# Sheet1.net
KiCad netlist of a schematic drawn in Altium Designer
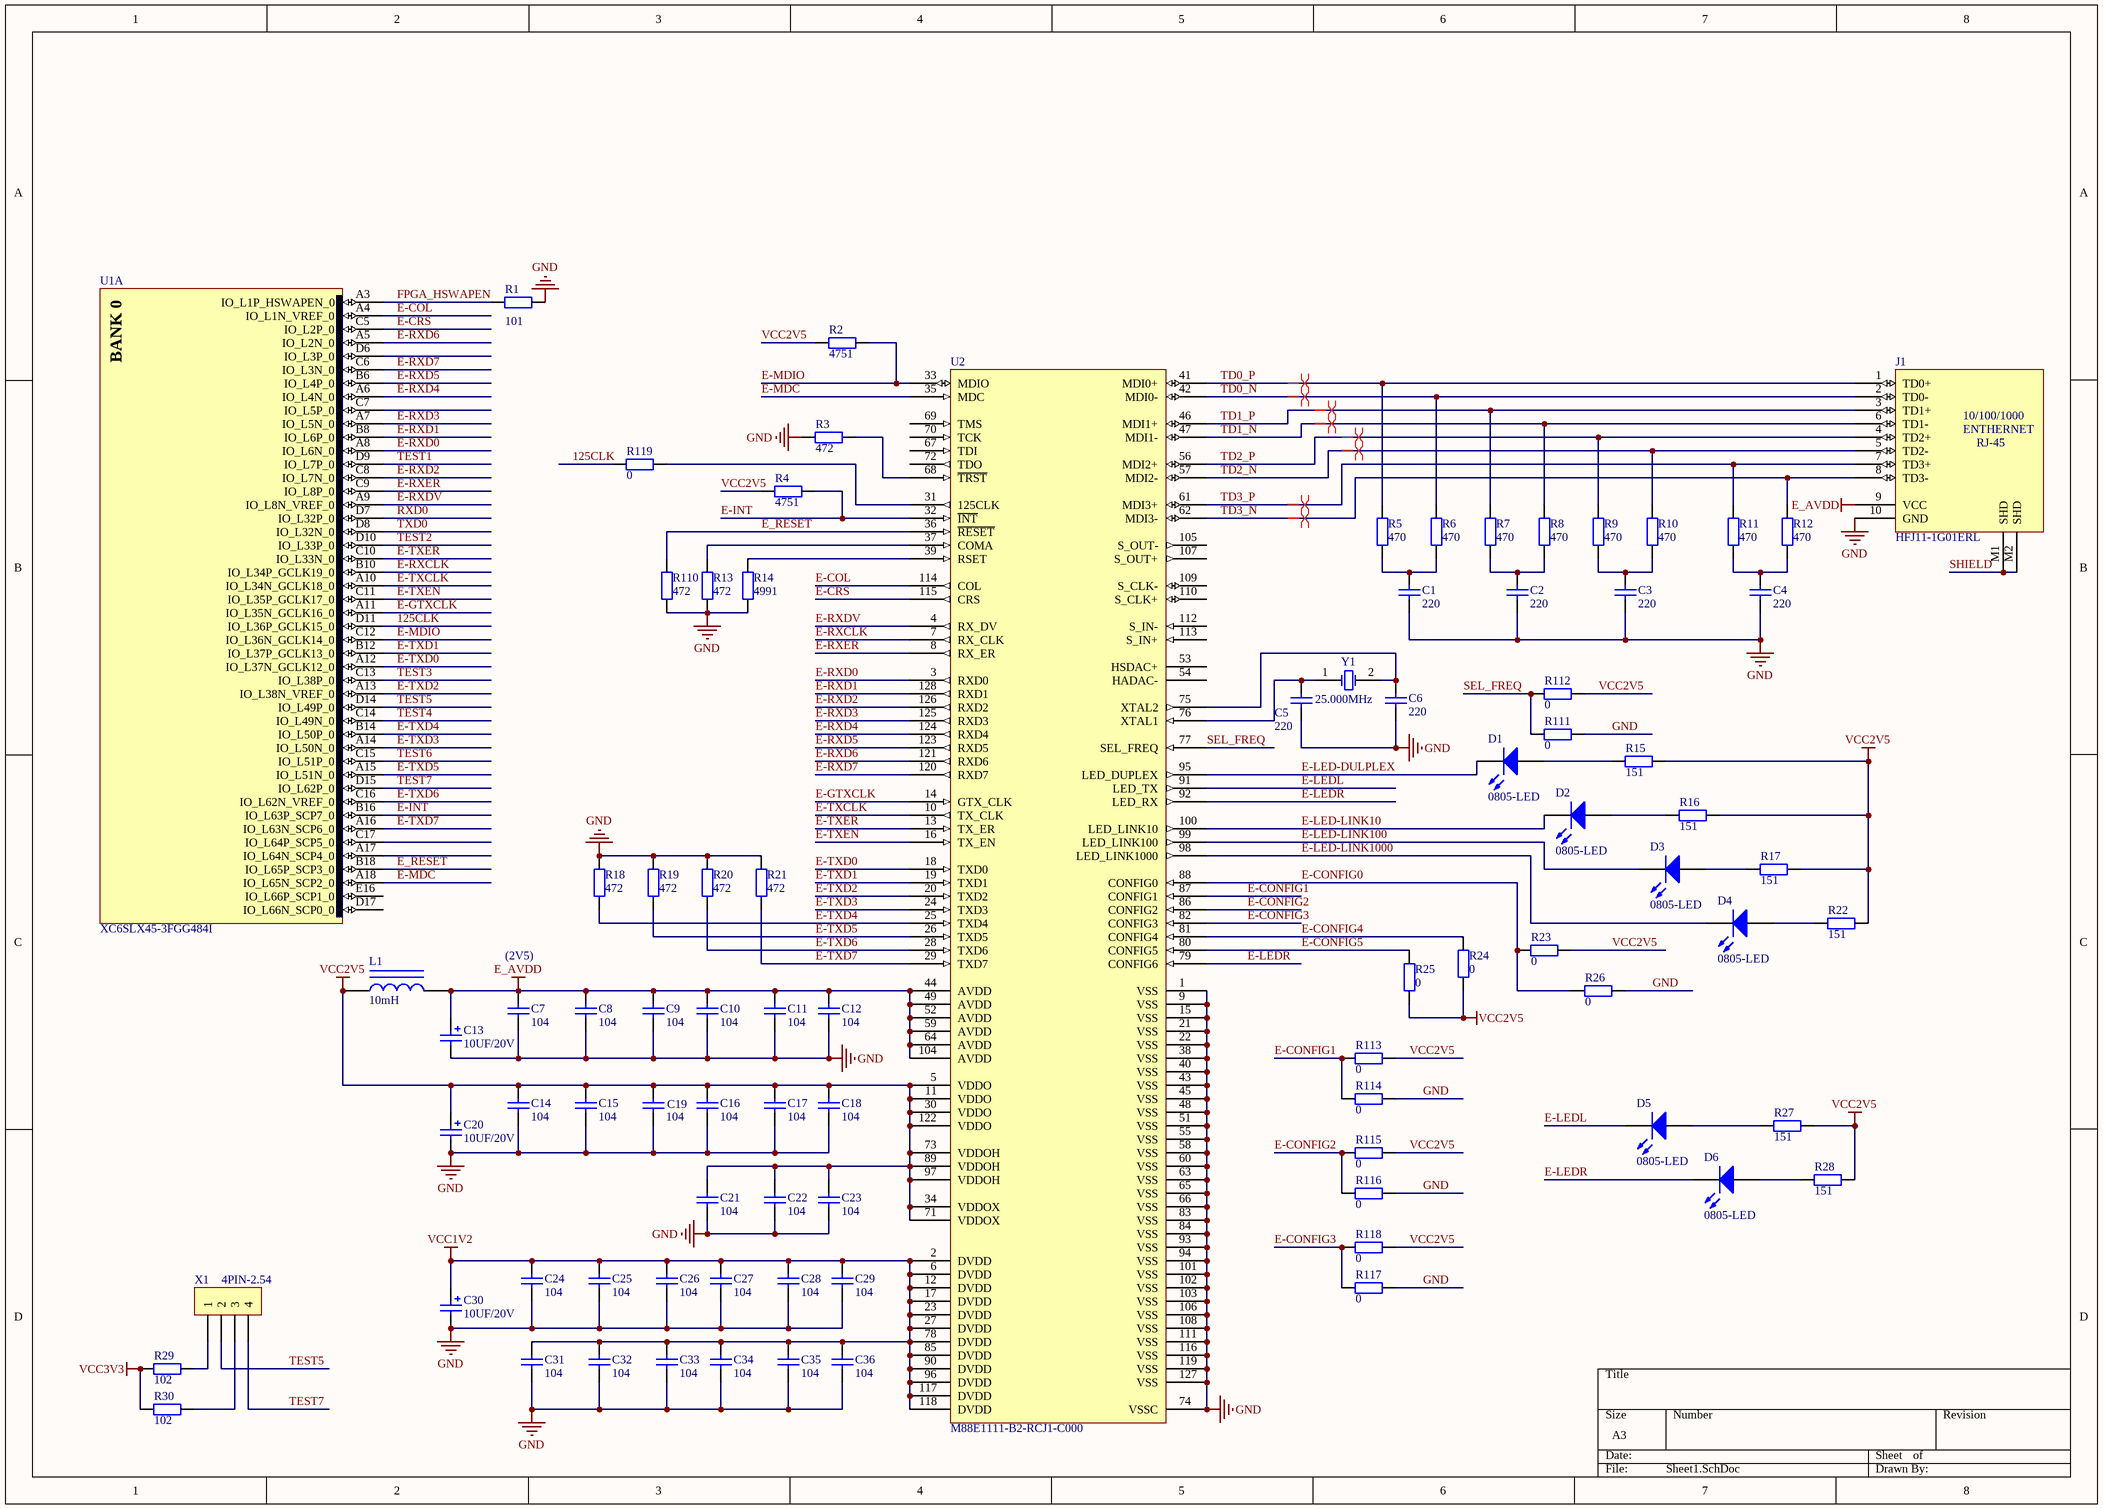
[diagram p0: Sheet1.SchDoc]

(export (version "E")
  (design (tool "Eeschema 10.0.6"))
  (components
    (comp (ref "C1")
      (value "220")
      (footprint "0402")
      (description "Capacitor")
      (fields (field (name "PUBLISHER") "Altium Limited"))
      (libsource (lib "Miscellaneous Devices") (part "Cap"))
    )
    (comp (ref "C2")
      (value "220")
      (footprint "0402")
      (description "Capacitor")
      (fields (field (name "PUBLISHER") "Altium Limited"))
      (libsource (lib "Miscellaneous Devices") (part "Cap"))
    )
    (comp (ref "C3")
      (value "220")
      (footprint "0402")
      (description "Capacitor")
      (fields (field (name "PUBLISHER") "Altium Limited"))
      (libsource (lib "Miscellaneous Devices") (part "Cap"))
    )
    (comp (ref "C4")
      (value "220")
      (footprint "0402")
      (description "Capacitor")
      (fields (field (name "PUBLISHER") "Altium Limited"))
      (libsource (lib "Miscellaneous Devices") (part "Cap"))
    )
    (comp (ref "C5")
      (value "220")
      (footprint "0402")
      (description "Capacitor")
      (fields (field (name "PUBLISHER") "Altium Limited"))
      (libsource (lib "Miscellaneous Devices") (part "Cap"))
    )
    (comp (ref "C6")
      (value "220")
      (footprint "0402")
      (description "Capacitor")
      (fields (field (name "PUBLISHER") "Altium Limited"))
      (libsource (lib "Miscellaneous Devices") (part "Cap"))
    )
    (comp (ref "C7")
      (value "104")
      (footprint "0402")
      (description "Capacitor")
      (fields (field (name "PUBLISHER") "Altium Limited"))
      (libsource (lib "Miscellaneous Devices") (part "Cap"))
    )
    (comp (ref "C8")
      (value "104")
      (footprint "0402")
      (description "Capacitor")
      (fields (field (name "PUBLISHER") "Altium Limited"))
      (libsource (lib "Miscellaneous Devices") (part "Cap"))
    )
    (comp (ref "C9")
      (value "104")
      (footprint "0402")
      (description "Capacitor")
      (fields (field (name "PUBLISHER") "Altium Limited"))
      (libsource (lib "Miscellaneous Devices") (part "Cap"))
    )
    (comp (ref "C10")
      (value "104")
      (footprint "0402")
      (description "Capacitor")
      (fields (field (name "PUBLISHER") "Altium Limited"))
      (libsource (lib "Miscellaneous Devices") (part "Cap"))
    )
    (comp (ref "C11")
      (value "104")
      (footprint "0402")
      (description "Capacitor")
      (fields (field (name "PUBLISHER") "Altium Limited"))
      (libsource (lib "Miscellaneous Devices") (part "Cap"))
    )
    (comp (ref "C12")
      (value "104")
      (footprint "0402")
      (description "Capacitor")
      (fields (field (name "PUBLISHER") "Altium Limited"))
      (libsource (lib "Miscellaneous Devices") (part "Cap"))
    )
    (comp (ref "C13")
      (value "10UF/20V")
      (footprint "CAP-B")
      (description "Polarized Capacitor (Axial)")
      (fields (field (name "PUBLISHER") "Altium Limited"))
      (libsource (lib "Miscellaneous Devices") (part "Cap Pol2"))
    )
    (comp (ref "C14")
      (value "104")
      (footprint "0402")
      (description "Capacitor")
      (fields (field (name "PUBLISHER") "Altium Limited"))
      (libsource (lib "Miscellaneous Devices") (part "Cap"))
    )
    (comp (ref "C15")
      (value "104")
      (footprint "0402")
      (description "Capacitor")
      (fields (field (name "PUBLISHER") "Altium Limited"))
      (libsource (lib "Miscellaneous Devices") (part "Cap"))
    )
    (comp (ref "C16")
      (value "104")
      (footprint "0402")
      (description "Capacitor")
      (fields (field (name "PUBLISHER") "Altium Limited"))
      (libsource (lib "Miscellaneous Devices") (part "Cap"))
    )
    (comp (ref "C17")
      (value "104")
      (footprint "0402")
      (description "Capacitor")
      (fields (field (name "PUBLISHER") "Altium Limited"))
      (libsource (lib "Miscellaneous Devices") (part "Cap"))
    )
    (comp (ref "C18")
      (value "104")
      (footprint "0402")
      (description "Capacitor")
      (fields (field (name "PUBLISHER") "Altium Limited"))
      (libsource (lib "Miscellaneous Devices") (part "Cap"))
    )
    (comp (ref "C19")
      (value "104")
      (footprint "0402")
      (description "Capacitor")
      (fields (field (name "PUBLISHER") "Altium Limited"))
      (libsource (lib "Miscellaneous Devices") (part "Cap"))
    )
    (comp (ref "C20")
      (value "10UF/20V")
      (footprint "CAP-B")
      (description "Polarized Capacitor (Axial)")
      (fields (field (name "PUBLISHER") "Altium Limited"))
      (libsource (lib "Miscellaneous Devices") (part "Cap Pol2"))
    )
    (comp (ref "C21")
      (value "104")
      (footprint "0402")
      (description "Capacitor")
      (fields (field (name "PUBLISHER") "Altium Limited"))
      (libsource (lib "Miscellaneous Devices") (part "Cap"))
    )
    (comp (ref "C22")
      (value "104")
      (footprint "0402")
      (description "Capacitor")
      (fields (field (name "PUBLISHER") "Altium Limited"))
      (libsource (lib "Miscellaneous Devices") (part "Cap"))
    )
    (comp (ref "C23")
      (value "104")
      (footprint "0402")
      (description "Capacitor")
      (fields (field (name "PUBLISHER") "Altium Limited"))
      (libsource (lib "Miscellaneous Devices") (part "Cap"))
    )
    (comp (ref "C24")
      (value "104")
      (footprint "0402")
      (description "Capacitor")
      (fields (field (name "PUBLISHER") "Altium Limited"))
      (libsource (lib "Miscellaneous Devices") (part "Cap"))
    )
    (comp (ref "C25")
      (value "104")
      (footprint "0402")
      (description "Capacitor")
      (fields (field (name "PUBLISHER") "Altium Limited"))
      (libsource (lib "Miscellaneous Devices") (part "Cap"))
    )
    (comp (ref "C26")
      (value "104")
      (footprint "0402")
      (description "Capacitor")
      (fields (field (name "PUBLISHER") "Altium Limited"))
      (libsource (lib "Miscellaneous Devices") (part "Cap"))
    )
    (comp (ref "C27")
      (value "104")
      (footprint "0402")
      (description "Capacitor")
      (fields (field (name "PUBLISHER") "Altium Limited"))
      (libsource (lib "Miscellaneous Devices") (part "Cap"))
    )
    (comp (ref "C28")
      (value "104")
      (footprint "0402")
      (description "Capacitor")
      (fields (field (name "PUBLISHER") "Altium Limited"))
      (libsource (lib "Miscellaneous Devices") (part "Cap"))
    )
    (comp (ref "C29")
      (value "104")
      (footprint "0402")
      (description "Capacitor")
      (fields (field (name "PUBLISHER") "Altium Limited"))
      (libsource (lib "Miscellaneous Devices") (part "Cap"))
    )
    (comp (ref "C30")
      (value "10UF/20V")
      (footprint "CAP-B")
      (description "Polarized Capacitor (Axial)")
      (fields (field (name "PUBLISHER") "Altium Limited"))
      (libsource (lib "Miscellaneous Devices") (part "Cap Pol2"))
    )
    (comp (ref "C31")
      (value "104")
      (footprint "0402")
      (description "Capacitor")
      (fields (field (name "PUBLISHER") "Altium Limited"))
      (libsource (lib "Miscellaneous Devices") (part "Cap"))
    )
    (comp (ref "C32")
      (value "104")
      (footprint "0402")
      (description "Capacitor")
      (fields (field (name "PUBLISHER") "Altium Limited"))
      (libsource (lib "Miscellaneous Devices") (part "Cap"))
    )
    (comp (ref "C33")
      (value "104")
      (footprint "0402")
      (description "Capacitor")
      (fields (field (name "PUBLISHER") "Altium Limited"))
      (libsource (lib "Miscellaneous Devices") (part "Cap"))
    )
    (comp (ref "C34")
      (value "104")
      (footprint "0402")
      (description "Capacitor")
      (fields (field (name "PUBLISHER") "Altium Limited"))
      (libsource (lib "Miscellaneous Devices") (part "Cap"))
    )
    (comp (ref "C35")
      (value "104")
      (footprint "0402")
      (description "Capacitor")
      (fields (field (name "PUBLISHER") "Altium Limited"))
      (libsource (lib "Miscellaneous Devices") (part "Cap"))
    )
    (comp (ref "C36")
      (value "104")
      (footprint "0402")
      (description "Capacitor")
      (fields (field (name "PUBLISHER") "Altium Limited"))
      (libsource (lib "Miscellaneous Devices") (part "Cap"))
    )
    (comp (ref "D1")
      (value "0805-LED")
      (footprint "0805LED")
      (description "Typical INFRARED GaAs LED")
      (fields (field (name "PUBLISHER") "Altium Limited"))
      (libsource (lib "Miscellaneous Devices") (part "LED0"))
    )
    (comp (ref "D2")
      (value "0805-LED")
      (footprint "0805LED")
      (description "Typical INFRARED GaAs LED")
      (fields (field (name "PUBLISHER") "Altium Limited"))
      (libsource (lib "Miscellaneous Devices") (part "LED0"))
    )
    (comp (ref "D3")
      (value "0805-LED")
      (footprint "0805LED")
      (description "Typical INFRARED GaAs LED")
      (fields (field (name "PUBLISHER") "Altium Limited"))
      (libsource (lib "Miscellaneous Devices") (part "LED0"))
    )
    (comp (ref "D4")
      (value "0805-LED")
      (footprint "0805LED")
      (description "Typical INFRARED GaAs LED")
      (fields (field (name "PUBLISHER") "Altium Limited"))
      (libsource (lib "Miscellaneous Devices") (part "LED0"))
    )
    (comp (ref "D5")
      (value "0805-LED")
      (footprint "0805LED")
      (description "Typical INFRARED GaAs LED")
      (fields (field (name "PUBLISHER") "Altium Limited"))
      (libsource (lib "Miscellaneous Devices") (part "LED0"))
    )
    (comp (ref "D6")
      (value "0805-LED")
      (footprint "0805LED")
      (description "Typical INFRARED GaAs LED")
      (fields (field (name "PUBLISHER") "Altium Limited"))
      (libsource (lib "Miscellaneous Devices") (part "LED0"))
    )
    (comp (ref "J1")
      (value "HFJ11-1G01ERL")
      (footprint "HFJ11-1G01ERL")
      (libsource (lib "Schlib1") (part "ETHERNET-RJ45"))
    )
    (comp (ref "L1")
      (value "10mH")
      (footprint "1206A")
      (description "Magnetic-Core Inductor")
      (fields (field (name "PUBLISHER") "Altium Limited"))
      (libsource (lib "Miscellaneous Devices") (part "Inductor Iron"))
    )
    (comp (ref "R1")
      (value "101")
      (footprint "0603")
      (description "Resistor")
      (fields (field (name "PUBLISHER") "Altium Limited"))
      (libsource (lib "Miscellaneous Devices") (part "Res2"))
    )
    (comp (ref "R2")
      (value "4751")
      (footprint "0603")
      (description "Resistor")
      (fields (field (name "PUBLISHER") "Altium Limited"))
      (libsource (lib "") (part "Res2_3"))
    )
    (comp (ref "R3")
      (value "472")
      (footprint "0603")
      (description "Resistor")
      (fields (field (name "PUBLISHER") "Altium Limited"))
      (libsource (lib "") (part "Res2_3"))
    )
    (comp (ref "R4")
      (value "4751")
      (footprint "0603")
      (description "Resistor")
      (fields (field (name "PUBLISHER") "Altium Limited"))
      (libsource (lib "") (part "Res2_3"))
    )
    (comp (ref "R5")
      (value "470")
      (footprint "0603")
      (description "Resistor")
      (fields (field (name "PUBLISHER") "Altium Limited"))
      (libsource (lib "") (part "Res2_1"))
    )
    (comp (ref "R6")
      (value "470")
      (footprint "0603")
      (description "Resistor")
      (fields (field (name "PUBLISHER") "Altium Limited"))
      (libsource (lib "") (part "Res2_1"))
    )
    (comp (ref "R7")
      (value "470")
      (footprint "0603")
      (description "Resistor")
      (fields (field (name "PUBLISHER") "Altium Limited"))
      (libsource (lib "") (part "Res2_1"))
    )
    (comp (ref "R8")
      (value "470")
      (footprint "0603")
      (description "Resistor")
      (fields (field (name "PUBLISHER") "Altium Limited"))
      (libsource (lib "") (part "Res2_1"))
    )
    (comp (ref "R9")
      (value "470")
      (footprint "0603")
      (description "Resistor")
      (fields (field (name "PUBLISHER") "Altium Limited"))
      (libsource (lib "") (part "Res2_1"))
    )
    (comp (ref "R10")
      (value "470")
      (footprint "0603")
      (description "Resistor")
      (fields (field (name "PUBLISHER") "Altium Limited"))
      (libsource (lib "") (part "Res2_1"))
    )
    (comp (ref "R11")
      (value "470")
      (footprint "0603")
      (description "Resistor")
      (fields (field (name "PUBLISHER") "Altium Limited"))
      (libsource (lib "") (part "Res2_1"))
    )
    (comp (ref "R12")
      (value "470")
      (footprint "0603")
      (description "Resistor")
      (fields (field (name "PUBLISHER") "Altium Limited"))
      (libsource (lib "") (part "Res2_1"))
    )
    (comp (ref "R13")
      (value "472")
      (footprint "0603")
      (description "Resistor")
      (fields (field (name "PUBLISHER") "Altium Limited"))
      (libsource (lib "") (part "Res2_1"))
    )
    (comp (ref "R14")
      (value "4991")
      (footprint "0603")
      (description "Resistor")
      (fields (field (name "PUBLISHER") "Altium Limited"))
      (libsource (lib "") (part "Res2_1"))
    )
    (comp (ref "R15")
      (value "151")
      (footprint "0603")
      (description "Resistor")
      (fields (field (name "PUBLISHER") "Altium Limited"))
      (libsource (lib "Miscellaneous Devices") (part "Res2"))
    )
    (comp (ref "R16")
      (value "151")
      (footprint "0603")
      (description "Resistor")
      (fields (field (name "PUBLISHER") "Altium Limited"))
      (libsource (lib "Miscellaneous Devices") (part "Res2"))
    )
    (comp (ref "R17")
      (value "151")
      (footprint "0603")
      (description "Resistor")
      (fields (field (name "PUBLISHER") "Altium Limited"))
      (libsource (lib "Miscellaneous Devices") (part "Res2"))
    )
    (comp (ref "R18")
      (value "472")
      (footprint "0603")
      (description "Resistor")
      (fields (field (name "PUBLISHER") "Altium Limited"))
      (libsource (lib "") (part "Res2_1"))
    )
    (comp (ref "R19")
      (value "472")
      (footprint "0603")
      (description "Resistor")
      (fields (field (name "PUBLISHER") "Altium Limited"))
      (libsource (lib "") (part "Res2_1"))
    )
    (comp (ref "R20")
      (value "472")
      (footprint "0603")
      (description "Resistor")
      (fields (field (name "PUBLISHER") "Altium Limited"))
      (libsource (lib "") (part "Res2_1"))
    )
    (comp (ref "R21")
      (value "472")
      (footprint "0603")
      (description "Resistor")
      (fields (field (name "PUBLISHER") "Altium Limited"))
      (libsource (lib "") (part "Res2_1"))
    )
    (comp (ref "R22")
      (value "151")
      (footprint "0603")
      (description "Resistor")
      (fields (field (name "PUBLISHER") "Altium Limited"))
      (libsource (lib "Miscellaneous Devices") (part "Res2"))
    )
    (comp (ref "R23")
      (value "0")
      (footprint "0603")
      (description "Resistor")
      (fields (field (name "PUBLISHER") "Altium Limited"))
      (libsource (lib "Miscellaneous Devices") (part "Res2"))
    )
    (comp (ref "R24")
      (value "0")
      (footprint "0603")
      (description "Resistor")
      (fields (field (name "PUBLISHER") "Altium Limited"))
      (libsource (lib "") (part "Res2_2"))
    )
    (comp (ref "R25")
      (value "0")
      (footprint "0603")
      (description "Resistor")
      (fields (field (name "PUBLISHER") "Altium Limited"))
      (libsource (lib "") (part "Res2_2"))
    )
    (comp (ref "R26")
      (value "0")
      (footprint "0603")
      (description "Resistor")
      (fields (field (name "PUBLISHER") "Altium Limited"))
      (libsource (lib "Miscellaneous Devices") (part "Res2"))
    )
    (comp (ref "R27")
      (value "151")
      (footprint "0603")
      (description "Resistor")
      (fields (field (name "PUBLISHER") "Altium Limited"))
      (libsource (lib "Miscellaneous Devices") (part "Res2"))
    )
    (comp (ref "R28")
      (value "151")
      (footprint "0603")
      (description "Resistor")
      (fields (field (name "PUBLISHER") "Altium Limited"))
      (libsource (lib "Miscellaneous Devices") (part "Res2"))
    )
    (comp (ref "R29")
      (value "102")
      (footprint "0603")
      (description "Resistor")
      (fields (field (name "PUBLISHER") "Altium Limited"))
      (libsource (lib "") (part "Res2_3"))
    )
    (comp (ref "R30")
      (value "102")
      (footprint "0603")
      (description "Resistor")
      (fields (field (name "PUBLISHER") "Altium Limited"))
      (libsource (lib "") (part "Res2_3"))
    )
    (comp (ref "R110")
      (value "472")
      (footprint "0603")
      (description "Resistor")
      (fields (field (name "PUBLISHER") "Altium Limited"))
      (libsource (lib "") (part "Res2_1"))
    )
    (comp (ref "R111")
      (value "0")
      (footprint "0402")
      (description "Resistor")
      (fields (field (name "PUBLISHER") "Altium Limited"))
      (libsource (lib "Miscellaneous Devices") (part "Res2"))
    )
    (comp (ref "R112")
      (value "0")
      (footprint "0402")
      (description "Resistor")
      (fields (field (name "PUBLISHER") "Altium Limited"))
      (libsource (lib "Miscellaneous Devices") (part "Res2"))
    )
    (comp (ref "R113")
      (value "0")
      (footprint "0402")
      (description "Resistor")
      (fields (field (name "PUBLISHER") "Altium Limited"))
      (libsource (lib "Miscellaneous Devices") (part "Res2"))
    )
    (comp (ref "R114")
      (value "0")
      (footprint "0402")
      (description "Resistor")
      (fields (field (name "PUBLISHER") "Altium Limited"))
      (libsource (lib "Miscellaneous Devices") (part "Res2"))
    )
    (comp (ref "R115")
      (value "0")
      (footprint "0402")
      (description "Resistor")
      (fields (field (name "PUBLISHER") "Altium Limited"))
      (libsource (lib "Miscellaneous Devices") (part "Res2"))
    )
    (comp (ref "R116")
      (value "0")
      (footprint "0402")
      (description "Resistor")
      (fields (field (name "PUBLISHER") "Altium Limited"))
      (libsource (lib "Miscellaneous Devices") (part "Res2"))
    )
    (comp (ref "R117")
      (value "0")
      (footprint "0402")
      (description "Resistor")
      (fields (field (name "PUBLISHER") "Altium Limited"))
      (libsource (lib "Miscellaneous Devices") (part "Res2"))
    )
    (comp (ref "R118")
      (value "0")
      (footprint "0402")
      (description "Resistor")
      (fields (field (name "PUBLISHER") "Altium Limited"))
      (libsource (lib "Miscellaneous Devices") (part "Res2"))
    )
    (comp (ref "R119")
      (value "0")
      (footprint "0603")
      (description "Resistor")
      (fields (field (name "PUBLISHER") "Altium Limited"))
      (libsource (lib "Miscellaneous Devices") (part "Res2"))
    )
    (comp (ref "U1")
      (value "XC6SLX45-3FGG484I")
      (footprint "FGG484")
      (fields (field (name "PUBLISHER") "Altium Limited"))
      (libsource (lib "Xilinx Spartan-6") (part "XC6SLX45-3FGG484I"))
    )
    (comp (ref "U2")
      (value "M88E1111-B2-RCJ1-C000")
      (footprint "SQFP50P1720X2320-128L")
      (libsource (lib "Schlib1") (part "Component_1"))
    )
    (comp (ref "X1")
      (value "4PIN-2.54")
      (footprint "SIP4X")
      (description "Connector")
      (libsource (lib "*") (part "CON4"))
    )
    (comp (ref "Y1")
      (value "25.000MHz")
      (footprint "CRYSTAL_2")
      (description "Crystal Oscillator")
      (fields (field (name "PUBLISHER") "Altium Limited"))
      (libsource (lib "Miscellaneous Devices") (part "XTAL"))
    )
  )
  (nets
    (net (code "1") (name "/125CLK") (class "Default")
      (node (ref "R119") (pin "2") (pinfunction "2_2") (pintype "passive"))
      (node (ref "U1") (pin "D11") (pinfunction "IO_L36P_GCLK15_0_D11") (pintype "bidirectional"))
    )
    (net (code "2") (name "/E-COL") (class "Default")
      (node (ref "U1") (pin "A4") (pinfunction "IO_L1N_VREF_0_A4") (pintype "bidirectional"))
      (node (ref "U2") (pin "114") (pinfunction "COL_114") (pintype "output"))
    )
    (net (code "3") (name "/E-CONFIG0") (class "Default")
      (node (ref "R23") (pin "2") (pinfunction "2_2") (pintype "passive"))
      (node (ref "R26") (pin "2") (pinfunction "2_2") (pintype "passive"))
      (node (ref "U2") (pin "88") (pinfunction "CONFIG0_88") (pintype "input"))
    )
    (net (code "4") (name "/E-CONFIG1") (class "Default")
      (node (ref "R113") (pin "2") (pinfunction "2_2") (pintype "passive"))
      (node (ref "R114") (pin "2") (pinfunction "2_2") (pintype "passive"))
      (node (ref "U2") (pin "87") (pinfunction "CONFIG1_87") (pintype "input"))
    )
    (net (code "5") (name "/E-CONFIG2") (class "Default")
      (node (ref "R115") (pin "2") (pinfunction "2_2") (pintype "passive"))
      (node (ref "R116") (pin "2") (pinfunction "2_2") (pintype "passive"))
      (node (ref "U2") (pin "86") (pinfunction "CONFIG2_86") (pintype "input"))
    )
    (net (code "6") (name "/E-CONFIG3") (class "Default")
      (node (ref "R117") (pin "2") (pinfunction "2_2") (pintype "passive"))
      (node (ref "R118") (pin "2") (pinfunction "2_2") (pintype "passive"))
      (node (ref "U2") (pin "82") (pinfunction "CONFIG3_82") (pintype "input"))
    )
    (net (code "7") (name "/E-CONFIG4") (class "Default")
      (node (ref "R24") (pin "1") (pinfunction "1_1") (pintype "passive"))
      (node (ref "U2") (pin "81") (pinfunction "CONFIG4_81") (pintype "input"))
    )
    (net (code "8") (name "/E-CONFIG5") (class "Default")
      (node (ref "R25") (pin "1") (pinfunction "1_1") (pintype "passive"))
      (node (ref "U2") (pin "80") (pinfunction "CONFIG5_80") (pintype "input"))
    )
    (net (code "9") (name "/E-CRS") (class "Default")
      (node (ref "U1") (pin "C5") (pinfunction "IO_L2P_0_C5") (pintype "bidirectional"))
      (node (ref "U2") (pin "115") (pinfunction "CRS_115") (pintype "output"))
    )
    (net (code "10") (name "/E-GTXCLK") (class "Default")
      (node (ref "U1") (pin "A11") (pinfunction "IO_L35N_GCLK16_0_A11") (pintype "bidirectional"))
      (node (ref "U2") (pin "14") (pinfunction "GTX_CLK_14") (pintype "input"))
    )
    (net (code "11") (name "/E-INT") (class "Default")
      (node (ref "R4") (pin "2") (pinfunction "2_2") (pintype "passive"))
      (node (ref "U1") (pin "B16") (pinfunction "IO_L63P_SCP7_0_B16") (pintype "bidirectional"))
      (node (ref "U2") (pin "32") (pinfunction "~{INT}_32") (pintype "input"))
    )
    (net (code "12") (name "/E-LED-DULPLEX") (class "Default")
      (node (ref "D1") (pin "2") (pinfunction "K_2") (pintype "passive"))
      (node (ref "U2") (pin "95") (pinfunction "LED_DUPLEX_95") (pintype "output"))
    )
    (net (code "13") (name "/E-LED-LINK10") (class "Default")
      (node (ref "D2") (pin "2") (pinfunction "K_2") (pintype "passive"))
      (node (ref "U2") (pin "100") (pinfunction "LED_LINK10_100") (pintype "output"))
    )
    (net (code "14") (name "/E-LED-LINK100") (class "Default")
      (node (ref "D3") (pin "2") (pinfunction "K_2") (pintype "passive"))
      (node (ref "U2") (pin "99") (pinfunction "LED_LINK100_99") (pintype "output"))
    )
    (net (code "15") (name "/E-LED-LINK1000") (class "Default")
      (node (ref "D4") (pin "2") (pinfunction "K_2") (pintype "passive"))
      (node (ref "U2") (pin "98") (pinfunction "LED_LINK1000_98") (pintype "output"))
    )
    (net (code "16") (name "/E-LEDL") (class "Default")
      (node (ref "D5") (pin "2") (pinfunction "K_2") (pintype "passive"))
      (node (ref "U2") (pin "91") (pinfunction "LED_TX_91") (pintype "output"))
    )
    (net (code "17") (name "/E-LEDR") (class "Default")
      (node (ref "D6") (pin "2") (pinfunction "K_2") (pintype "passive"))
      (node (ref "U2") (pin "79") (pinfunction "CONFIG6_79") (pintype "input"))
      (node (ref "U2") (pin "92") (pinfunction "LED_RX_92") (pintype "output"))
    )
    (net (code "18") (name "/E-MDC") (class "Default")
      (node (ref "U1") (pin "A18") (pinfunction "IO_L65N_SCP2_0_A18") (pintype "bidirectional"))
      (node (ref "U2") (pin "35") (pinfunction "MDC_35") (pintype "input"))
    )
    (net (code "19") (name "/E-MDIO") (class "Default")
      (node (ref "R2") (pin "2") (pinfunction "2_2") (pintype "passive"))
      (node (ref "U1") (pin "C12") (pinfunction "IO_L36N_GCLK14_0_C12") (pintype "bidirectional"))
      (node (ref "U2") (pin "33") (pinfunction "MDIO_33") (pintype "bidirectional"))
    )
    (net (code "20") (name "/E-RXCLK") (class "Default")
      (node (ref "U1") (pin "B10") (pinfunction "IO_L34P_GCLK19_0_B10") (pintype "bidirectional"))
      (node (ref "U2") (pin "7") (pinfunction "RX_CLK_7") (pintype "output"))
    )
    (net (code "21") (name "/E-RXD0") (class "Default")
      (node (ref "U1") (pin "A8") (pinfunction "IO_L6N_0_A8") (pintype "bidirectional"))
      (node (ref "U2") (pin "3") (pinfunction "RXD0_3") (pintype "output"))
    )
    (net (code "22") (name "/E-RXD1") (class "Default")
      (node (ref "U1") (pin "B8") (pinfunction "IO_L6P_0_B8") (pintype "bidirectional"))
      (node (ref "U2") (pin "128") (pinfunction "RXD1_128") (pintype "output"))
    )
    (net (code "23") (name "/E-RXD2") (class "Default")
      (node (ref "U1") (pin "C8") (pinfunction "IO_L7N_0_C8") (pintype "bidirectional"))
      (node (ref "U2") (pin "126") (pinfunction "RXD2_126") (pintype "output"))
    )
    (net (code "24") (name "/E-RXD3") (class "Default")
      (node (ref "U1") (pin "A7") (pinfunction "IO_L5N_0_A7") (pintype "bidirectional"))
      (node (ref "U2") (pin "125") (pinfunction "RXD3_125") (pintype "output"))
    )
    (net (code "25") (name "/E-RXD4") (class "Default")
      (node (ref "U1") (pin "A6") (pinfunction "IO_L4N_0_A6") (pintype "bidirectional"))
      (node (ref "U2") (pin "124") (pinfunction "RXD4_124") (pintype "output"))
    )
    (net (code "26") (name "/E-RXD5") (class "Default")
      (node (ref "U1") (pin "B6") (pinfunction "IO_L4P_0_B6") (pintype "bidirectional"))
      (node (ref "U2") (pin "123") (pinfunction "RXD5_123") (pintype "output"))
    )
    (net (code "27") (name "/E-RXD6") (class "Default")
      (node (ref "U1") (pin "A5") (pinfunction "IO_L2N_0_A5") (pintype "bidirectional"))
      (node (ref "U2") (pin "121") (pinfunction "RXD6_121") (pintype "output"))
    )
    (net (code "28") (name "/E-RXD7") (class "Default")
      (node (ref "U1") (pin "C6") (pinfunction "IO_L3N_0_C6") (pintype "bidirectional"))
      (node (ref "U2") (pin "120") (pinfunction "RXD7_120") (pintype "output"))
    )
    (net (code "29") (name "/E-RXDV") (class "Default")
      (node (ref "U1") (pin "A9") (pinfunction "IO_L8N_VREF_0_A9") (pintype "bidirectional"))
      (node (ref "U2") (pin "4") (pinfunction "RX_DV_4") (pintype "output"))
    )
    (net (code "30") (name "/E-RXER") (class "Default")
      (node (ref "U1") (pin "C9") (pinfunction "IO_L8P_0_C9") (pintype "bidirectional"))
      (node (ref "U2") (pin "8") (pinfunction "RX_ER_8") (pintype "output"))
    )
    (net (code "31") (name "/E-TXCLK") (class "Default")
      (node (ref "U1") (pin "A10") (pinfunction "IO_L34N_GCLK18_0_A10") (pintype "bidirectional"))
      (node (ref "U2") (pin "10") (pinfunction "TX_CLK_10") (pintype "output"))
    )
    (net (code "32") (name "/E-TXD0") (class "Default")
      (node (ref "U1") (pin "A12") (pinfunction "IO_L37N_GCLK12_0_A12") (pintype "bidirectional"))
      (node (ref "U2") (pin "18") (pinfunction "TXD0_18") (pintype "input"))
    )
    (net (code "33") (name "/E-TXD1") (class "Default")
      (node (ref "U1") (pin "B12") (pinfunction "IO_L37P_GCLK13_0_B12") (pintype "bidirectional"))
      (node (ref "U2") (pin "19") (pinfunction "TXD1_19") (pintype "input"))
    )
    (net (code "34") (name "/E-TXD2") (class "Default")
      (node (ref "U1") (pin "A13") (pinfunction "IO_L38N_VREF_0_A13") (pintype "bidirectional"))
      (node (ref "U2") (pin "20") (pinfunction "TXD2_20") (pintype "input"))
    )
    (net (code "35") (name "/E-TXD3") (class "Default")
      (node (ref "U1") (pin "A14") (pinfunction "IO_L50N_0_A14") (pintype "bidirectional"))
      (node (ref "U2") (pin "24") (pinfunction "TXD3_24") (pintype "input"))
    )
    (net (code "36") (name "/E-TXD4") (class "Default")
      (node (ref "R18") (pin "1") (pinfunction "1_1") (pintype "passive"))
      (node (ref "U1") (pin "B14") (pinfunction "IO_L50P_0_B14") (pintype "bidirectional"))
      (node (ref "U2") (pin "25") (pinfunction "TXD4_25") (pintype "input"))
    )
    (net (code "37") (name "/E-TXD5") (class "Default")
      (node (ref "R19") (pin "1") (pinfunction "1_1") (pintype "passive"))
      (node (ref "U1") (pin "A15") (pinfunction "IO_L51N_0_A15") (pintype "bidirectional"))
      (node (ref "U2") (pin "26") (pinfunction "TXD5_26") (pintype "input"))
    )
    (net (code "38") (name "/E-TXD6") (class "Default")
      (node (ref "R20") (pin "1") (pinfunction "1_1") (pintype "passive"))
      (node (ref "U1") (pin "C16") (pinfunction "IO_L62N_VREF_0_C16") (pintype "bidirectional"))
      (node (ref "U2") (pin "28") (pinfunction "TXD6_28") (pintype "input"))
    )
    (net (code "39") (name "/E-TXD7") (class "Default")
      (node (ref "R21") (pin "1") (pinfunction "1_1") (pintype "passive"))
      (node (ref "U1") (pin "A16") (pinfunction "IO_L63N_SCP6_0_A16") (pintype "bidirectional"))
      (node (ref "U2") (pin "29") (pinfunction "TXD7_29") (pintype "input"))
    )
    (net (code "40") (name "/E-TXEN") (class "Default")
      (node (ref "U1") (pin "C11") (pinfunction "IO_L35P_GCLK17_0_C11") (pintype "bidirectional"))
      (node (ref "U2") (pin "16") (pinfunction "TX_EN_16") (pintype "input"))
    )
    (net (code "41") (name "/E-TXER") (class "Default")
      (node (ref "U1") (pin "C10") (pinfunction "IO_L33N_0_C10") (pintype "bidirectional"))
      (node (ref "U2") (pin "13") (pinfunction "TX_ER_13") (pintype "input"))
    )
    (net (code "42") (name "/E_RESET") (class "Default")
      (node (ref "R110") (pin "2") (pinfunction "2_2") (pintype "passive"))
      (node (ref "U1") (pin "B18") (pinfunction "IO_L65P_SCP3_0_B18") (pintype "bidirectional"))
      (node (ref "U2") (pin "36") (pinfunction "~{RESET}_36") (pintype "input"))
    )
    (net (code "43") (name "/FPGA_HSWAPEN") (class "Default")
      (node (ref "R1") (pin "2") (pinfunction "2_2") (pintype "passive"))
      (node (ref "U1") (pin "A3") (pinfunction "IO_L1P_HSWAPEN_0_A3") (pintype "bidirectional"))
    )
    (net (code "44") (name "/RXD0") (class "Default")
      (node (ref "U1") (pin "D7") (pinfunction "IO_L32P_0_D7") (pintype "bidirectional"))
    )
    (net (code "45") (name "/SEL_FREQ") (class "Default")
      (node (ref "R111") (pin "2") (pinfunction "2_2") (pintype "passive"))
      (node (ref "R112") (pin "2") (pinfunction "2_2") (pintype "passive"))
      (node (ref "U2") (pin "77") (pinfunction "SEL_FREQ_77") (pintype "input"))
    )
    (net (code "46") (name "/SHIELD") (class "Default")
      (node (ref "J1") (pin "M1") (pinfunction "SHD_M1") (pintype "passive"))
      (node (ref "J1") (pin "M2") (pinfunction "SHD_M2") (pintype "passive"))
    )
    (net (code "47") (name "/TD0_N") (class "Default")
      (node (ref "J1") (pin "2") (pinfunction "TD0-_2") (pintype "bidirectional"))
      (node (ref "R6") (pin "2") (pinfunction "2_2") (pintype "passive"))
      (node (ref "U2") (pin "42") (pinfunction "MDI0-_42") (pintype "bidirectional"))
    )
    (net (code "48") (name "/TD0_P") (class "Default")
      (node (ref "J1") (pin "1") (pinfunction "TD0+_1") (pintype "bidirectional"))
      (node (ref "R5") (pin "2") (pinfunction "2_2") (pintype "passive"))
      (node (ref "U2") (pin "41") (pinfunction "MDI0+_41") (pintype "bidirectional"))
    )
    (net (code "49") (name "/TD1_N") (class "Default")
      (node (ref "J1") (pin "6") (pinfunction "TD1-_6") (pintype "bidirectional"))
      (node (ref "R8") (pin "2") (pinfunction "2_2") (pintype "passive"))
      (node (ref "U2") (pin "47") (pinfunction "MDI1-_47") (pintype "bidirectional"))
    )
    (net (code "50") (name "/TD1_P") (class "Default")
      (node (ref "J1") (pin "3") (pinfunction "TD1+_3") (pintype "bidirectional"))
      (node (ref "R7") (pin "2") (pinfunction "2_2") (pintype "passive"))
      (node (ref "U2") (pin "46") (pinfunction "MDI1+_46") (pintype "bidirectional"))
    )
    (net (code "51") (name "/TD2_N") (class "Default")
      (node (ref "J1") (pin "5") (pinfunction "TD2-_5") (pintype "bidirectional"))
      (node (ref "R10") (pin "2") (pinfunction "2_2") (pintype "passive"))
      (node (ref "U2") (pin "57") (pinfunction "MDI2-_57") (pintype "bidirectional"))
    )
    (net (code "52") (name "/TD2_P") (class "Default")
      (node (ref "J1") (pin "4") (pinfunction "TD2+_4") (pintype "bidirectional"))
      (node (ref "R9") (pin "2") (pinfunction "2_2") (pintype "passive"))
      (node (ref "U2") (pin "56") (pinfunction "MDI2+_56") (pintype "bidirectional"))
    )
    (net (code "53") (name "/TD3_N") (class "Default")
      (node (ref "J1") (pin "8") (pinfunction "TD3-_8") (pintype "bidirectional"))
      (node (ref "R12") (pin "2") (pinfunction "2_2") (pintype "passive"))
      (node (ref "U2") (pin "62") (pinfunction "MDI3-_62") (pintype "bidirectional"))
    )
    (net (code "54") (name "/TD3_P") (class "Default")
      (node (ref "J1") (pin "7") (pinfunction "TD3+_7") (pintype "bidirectional"))
      (node (ref "R11") (pin "2") (pinfunction "2_2") (pintype "passive"))
      (node (ref "U2") (pin "61") (pinfunction "MDI3+_61") (pintype "bidirectional"))
    )
    (net (code "55") (name "/TEST1") (class "Default")
      (node (ref "U1") (pin "D9") (pinfunction "IO_L7P_0_D9") (pintype "bidirectional"))
    )
    (net (code "56") (name "/TEST2") (class "Default")
      (node (ref "U1") (pin "D10") (pinfunction "IO_L33P_0_D10") (pintype "bidirectional"))
    )
    (net (code "57") (name "/TEST3") (class "Default")
      (node (ref "U1") (pin "C13") (pinfunction "IO_L38P_0_C13") (pintype "bidirectional"))
    )
    (net (code "58") (name "/TEST4") (class "Default")
      (node (ref "U1") (pin "C14") (pinfunction "IO_L49N_0_C14") (pintype "bidirectional"))
    )
    (net (code "59") (name "/TEST5") (class "Default")
      (node (ref "U1") (pin "D14") (pinfunction "IO_L49P_0_D14") (pintype "bidirectional"))
      (node (ref "X1") (pin "2") (pinfunction "2_2") (pintype "passive"))
    )
    (net (code "60") (name "/TEST6") (class "Default")
      (node (ref "U1") (pin "C15") (pinfunction "IO_L51P_0_C15") (pintype "bidirectional"))
    )
    (net (code "61") (name "/TEST7") (class "Default")
      (node (ref "U1") (pin "D15") (pinfunction "IO_L62P_0_D15") (pintype "bidirectional"))
      (node (ref "X1") (pin "4") (pinfunction "4_4") (pintype "passive"))
    )
    (net (code "62") (name "/TXD0") (class "Default")
      (node (ref "U1") (pin "D8") (pinfunction "IO_L32N_0_D8") (pintype "bidirectional"))
    )
    (net (code "63") (name "E_AVDD") (class "Default")
      (node (ref "C10") (pin "2") (pinfunction "2_2") (pintype "passive"))
      (node (ref "C11") (pin "2") (pinfunction "2_2") (pintype "passive"))
      (node (ref "C12") (pin "2") (pinfunction "2_2") (pintype "passive"))
      (node (ref "C13") (pin "1") (pinfunction "1_1") (pintype "passive"))
      (node (ref "C7") (pin "2") (pinfunction "2_2") (pintype "passive"))
      (node (ref "C8") (pin "2") (pinfunction "2_2") (pintype "passive"))
      (node (ref "C9") (pin "2") (pinfunction "2_2") (pintype "passive"))
      (node (ref "J1") (pin "9") (pinfunction "VCC_9") (pintype "power_in"))
      (node (ref "L1") (pin "2") (pinfunction "2_2") (pintype "passive"))
      (node (ref "U2") (pin "104") (pinfunction "AVDD_104") (pintype "power_in"))
      (node (ref "U2") (pin "44") (pinfunction "AVDD_44") (pintype "power_in"))
      (node (ref "U2") (pin "49") (pinfunction "AVDD_49") (pintype "power_in"))
      (node (ref "U2") (pin "52") (pinfunction "AVDD_52") (pintype "power_in"))
      (node (ref "U2") (pin "59") (pinfunction "AVDD_59") (pintype "power_in"))
      (node (ref "U2") (pin "64") (pinfunction "AVDD_64") (pintype "power_in"))
    )
    (net (code "64") (name "GND") (class "Default")
      (node (ref "C1") (pin "1") (pinfunction "1_1") (pintype "passive"))
      (node (ref "C10") (pin "1") (pinfunction "1_1") (pintype "passive"))
      (node (ref "C11") (pin "1") (pinfunction "1_1") (pintype "passive"))
      (node (ref "C12") (pin "1") (pinfunction "1_1") (pintype "passive"))
      (node (ref "C13") (pin "2") (pinfunction "2_2") (pintype "passive"))
      (node (ref "C14") (pin "1") (pinfunction "1_1") (pintype "passive"))
      (node (ref "C15") (pin "1") (pinfunction "1_1") (pintype "passive"))
      (node (ref "C16") (pin "1") (pinfunction "1_1") (pintype "passive"))
      (node (ref "C17") (pin "1") (pinfunction "1_1") (pintype "passive"))
      (node (ref "C18") (pin "1") (pinfunction "1_1") (pintype "passive"))
      (node (ref "C19") (pin "1") (pinfunction "1_1") (pintype "passive"))
      (node (ref "C2") (pin "1") (pinfunction "1_1") (pintype "passive"))
      (node (ref "C20") (pin "2") (pinfunction "2_2") (pintype "passive"))
      (node (ref "C21") (pin "1") (pinfunction "1_1") (pintype "passive"))
      (node (ref "C22") (pin "1") (pinfunction "1_1") (pintype "passive"))
      (node (ref "C23") (pin "1") (pinfunction "1_1") (pintype "passive"))
      (node (ref "C24") (pin "1") (pinfunction "1_1") (pintype "passive"))
      (node (ref "C25") (pin "1") (pinfunction "1_1") (pintype "passive"))
      (node (ref "C26") (pin "1") (pinfunction "1_1") (pintype "passive"))
      (node (ref "C27") (pin "1") (pinfunction "1_1") (pintype "passive"))
      (node (ref "C28") (pin "1") (pinfunction "1_1") (pintype "passive"))
      (node (ref "C29") (pin "1") (pinfunction "1_1") (pintype "passive"))
      (node (ref "C3") (pin "1") (pinfunction "1_1") (pintype "passive"))
      (node (ref "C30") (pin "2") (pinfunction "2_2") (pintype "passive"))
      (node (ref "C31") (pin "1") (pinfunction "1_1") (pintype "passive"))
      (node (ref "C32") (pin "1") (pinfunction "1_1") (pintype "passive"))
      (node (ref "C33") (pin "1") (pinfunction "1_1") (pintype "passive"))
      (node (ref "C34") (pin "1") (pinfunction "1_1") (pintype "passive"))
      (node (ref "C35") (pin "1") (pinfunction "1_1") (pintype "passive"))
      (node (ref "C36") (pin "1") (pinfunction "1_1") (pintype "passive"))
      (node (ref "C4") (pin "1") (pinfunction "1_1") (pintype "passive"))
      (node (ref "C5") (pin "1") (pinfunction "1_1") (pintype "passive"))
      (node (ref "C6") (pin "1") (pinfunction "1_1") (pintype "passive"))
      (node (ref "C7") (pin "1") (pinfunction "1_1") (pintype "passive"))
      (node (ref "C8") (pin "1") (pinfunction "1_1") (pintype "passive"))
      (node (ref "C9") (pin "1") (pinfunction "1_1") (pintype "passive"))
      (node (ref "J1") (pin "10") (pinfunction "GND_10") (pintype "power_in"))
      (node (ref "R1") (pin "1") (pinfunction "1_1") (pintype "passive"))
      (node (ref "R110") (pin "1") (pinfunction "1_1") (pintype "passive"))
      (node (ref "R111") (pin "1") (pinfunction "1_1") (pintype "passive"))
      (node (ref "R114") (pin "1") (pinfunction "1_1") (pintype "passive"))
      (node (ref "R116") (pin "1") (pinfunction "1_1") (pintype "passive"))
      (node (ref "R117") (pin "1") (pinfunction "1_1") (pintype "passive"))
      (node (ref "R13") (pin "1") (pinfunction "1_1") (pintype "passive"))
      (node (ref "R14") (pin "1") (pinfunction "1_1") (pintype "passive"))
      (node (ref "R18") (pin "2") (pinfunction "2_2") (pintype "passive"))
      (node (ref "R19") (pin "2") (pinfunction "2_2") (pintype "passive"))
      (node (ref "R20") (pin "2") (pinfunction "2_2") (pintype "passive"))
      (node (ref "R21") (pin "2") (pinfunction "2_2") (pintype "passive"))
      (node (ref "R26") (pin "1") (pinfunction "1_1") (pintype "passive"))
      (node (ref "R3") (pin "1") (pinfunction "1_1") (pintype "passive"))
      (node (ref "U2") (pin "1") (pinfunction "VSS_1") (pintype "power_in"))
      (node (ref "U2") (pin "101") (pinfunction "VSS_101") (pintype "power_in"))
      (node (ref "U2") (pin "102") (pinfunction "VSS_102") (pintype "power_in"))
      (node (ref "U2") (pin "103") (pinfunction "VSS_103") (pintype "power_in"))
      (node (ref "U2") (pin "106") (pinfunction "VSS_106") (pintype "power_in"))
      (node (ref "U2") (pin "108") (pinfunction "VSS_108") (pintype "power_in"))
      (node (ref "U2") (pin "111") (pinfunction "VSS_111") (pintype "power_in"))
      (node (ref "U2") (pin "116") (pinfunction "VSS_116") (pintype "power_in"))
      (node (ref "U2") (pin "119") (pinfunction "VSS_119") (pintype "power_in"))
      (node (ref "U2") (pin "127") (pinfunction "VSS_127") (pintype "power_in"))
      (node (ref "U2") (pin "15") (pinfunction "VSS_15") (pintype "power_in"))
      (node (ref "U2") (pin "21") (pinfunction "VSS_21") (pintype "power_in"))
      (node (ref "U2") (pin "22") (pinfunction "VSS_22") (pintype "power_in"))
      (node (ref "U2") (pin "38") (pinfunction "VSS_38") (pintype "power_in"))
      (node (ref "U2") (pin "40") (pinfunction "VSS_40") (pintype "power_in"))
      (node (ref "U2") (pin "43") (pinfunction "VSS_43") (pintype "power_in"))
      (node (ref "U2") (pin "45") (pinfunction "VSS_45") (pintype "power_in"))
      (node (ref "U2") (pin "48") (pinfunction "VSS_48") (pintype "power_in"))
      (node (ref "U2") (pin "51") (pinfunction "VSS_51") (pintype "power_in"))
      (node (ref "U2") (pin "55") (pinfunction "VSS_55") (pintype "power_in"))
      (node (ref "U2") (pin "58") (pinfunction "VSS_58") (pintype "power_in"))
      (node (ref "U2") (pin "60") (pinfunction "VSS_60") (pintype "power_in"))
      (node (ref "U2") (pin "63") (pinfunction "VSS_63") (pintype "power_in"))
      (node (ref "U2") (pin "65") (pinfunction "VSS_65") (pintype "power_in"))
      (node (ref "U2") (pin "66") (pinfunction "VSS_66") (pintype "power_in"))
      (node (ref "U2") (pin "74") (pinfunction "VSSC_74") (pintype "power_in"))
      (node (ref "U2") (pin "83") (pinfunction "VSS_83") (pintype "power_in"))
      (node (ref "U2") (pin "84") (pinfunction "VSS_84") (pintype "power_in"))
      (node (ref "U2") (pin "9") (pinfunction "VSS_9") (pintype "power_in"))
      (node (ref "U2") (pin "93") (pinfunction "VSS_93") (pintype "power_in"))
      (node (ref "U2") (pin "94") (pinfunction "VSS_94") (pintype "power_in"))
    )
    (net (code "65") (name "Net-(C1-Pad2)") (class "Default")
      (node (ref "C1") (pin "2") (pinfunction "2_2") (pintype "passive"))
      (node (ref "R5") (pin "1") (pinfunction "1_1") (pintype "passive"))
      (node (ref "R6") (pin "1") (pinfunction "1_1") (pintype "passive"))
    )
    (net (code "66") (name "Net-(C2-Pad2)") (class "Default")
      (node (ref "C2") (pin "2") (pinfunction "2_2") (pintype "passive"))
      (node (ref "R7") (pin "1") (pinfunction "1_1") (pintype "passive"))
      (node (ref "R8") (pin "1") (pinfunction "1_1") (pintype "passive"))
    )
    (net (code "67") (name "Net-(C3-Pad2)") (class "Default")
      (node (ref "C3") (pin "2") (pinfunction "2_2") (pintype "passive"))
      (node (ref "R10") (pin "1") (pinfunction "1_1") (pintype "passive"))
      (node (ref "R9") (pin "1") (pinfunction "1_1") (pintype "passive"))
    )
    (net (code "68") (name "Net-(C4-Pad2)") (class "Default")
      (node (ref "C4") (pin "2") (pinfunction "2_2") (pintype "passive"))
      (node (ref "R11") (pin "1") (pinfunction "1_1") (pintype "passive"))
      (node (ref "R12") (pin "1") (pinfunction "1_1") (pintype "passive"))
    )
    (net (code "69") (name "Net-(D1-A)") (class "Default")
      (node (ref "D1") (pin "1") (pinfunction "A_1") (pintype "passive"))
      (node (ref "R15") (pin "2") (pinfunction "2_2") (pintype "passive"))
    )
    (net (code "70") (name "Net-(D2-A)") (class "Default")
      (node (ref "D2") (pin "1") (pinfunction "A_1") (pintype "passive"))
      (node (ref "R16") (pin "2") (pinfunction "2_2") (pintype "passive"))
    )
    (net (code "71") (name "Net-(D3-A)") (class "Default")
      (node (ref "D3") (pin "1") (pinfunction "A_1") (pintype "passive"))
      (node (ref "R17") (pin "2") (pinfunction "2_2") (pintype "passive"))
    )
    (net (code "72") (name "Net-(D4-A)") (class "Default")
      (node (ref "D4") (pin "1") (pinfunction "A_1") (pintype "passive"))
      (node (ref "R22") (pin "2") (pinfunction "2_2") (pintype "passive"))
    )
    (net (code "73") (name "Net-(D5-A)") (class "Default")
      (node (ref "D5") (pin "1") (pinfunction "A_1") (pintype "passive"))
      (node (ref "R27") (pin "2") (pinfunction "2_2") (pintype "passive"))
    )
    (net (code "74") (name "Net-(D6-A)") (class "Default")
      (node (ref "D6") (pin "1") (pinfunction "A_1") (pintype "passive"))
      (node (ref "R28") (pin "2") (pinfunction "2_2") (pintype "passive"))
    )
    (net (code "75") (name "Net-(R29-Pad2)") (class "Default")
      (node (ref "R29") (pin "2") (pinfunction "2_2") (pintype "passive"))
      (node (ref "X1") (pin "1") (pinfunction "1_1") (pintype "passive"))
    )
    (net (code "76") (name "Net-(R30-Pad2)") (class "Default")
      (node (ref "R30") (pin "2") (pinfunction "2_2") (pintype "passive"))
      (node (ref "X1") (pin "3") (pinfunction "3_3") (pintype "passive"))
    )
    (net (code "77") (name "Net-(U2-125CLK)") (class "Default")
      (node (ref "R119") (pin "1") (pinfunction "1_1") (pintype "passive"))
      (node (ref "U2") (pin "31") (pinfunction "125CLK_31") (pintype "output"))
    )
    (net (code "78") (name "Net-(U2-COMA)") (class "Default")
      (node (ref "R13") (pin "2") (pinfunction "2_2") (pintype "passive"))
      (node (ref "U2") (pin "37") (pinfunction "COMA_37") (pintype "input"))
    )
    (net (code "79") (name "Net-(U2-RSET)") (class "Default")
      (node (ref "R14") (pin "2") (pinfunction "2_2") (pintype "passive"))
      (node (ref "U2") (pin "39") (pinfunction "RSET_39") (pintype "input"))
    )
    (net (code "80") (name "Net-(U2-XTAL1)") (class "Default")
      (node (ref "C5") (pin "2") (pinfunction "2_2") (pintype "passive"))
      (node (ref "U2") (pin "76") (pinfunction "XTAL1_76") (pintype "input"))
      (node (ref "Y1") (pin "1") (pinfunction "OSC1_1") (pintype "passive"))
    )
    (net (code "81") (name "Net-(U2-XTAL2)") (class "Default")
      (node (ref "C6") (pin "2") (pinfunction "2_2") (pintype "passive"))
      (node (ref "U2") (pin "75") (pinfunction "XTAL2_75") (pintype "output"))
      (node (ref "Y1") (pin "2") (pinfunction "OSC2_2") (pintype "passive"))
    )
    (net (code "82") (name "Net-(U2-~{TRST})") (class "Default")
      (node (ref "R3") (pin "2") (pinfunction "2_2") (pintype "passive"))
      (node (ref "U2") (pin "68") (pinfunction "~{TRST}_68") (pintype "input"))
    )
    (net (code "83") (name "VCC1V2") (class "Default")
      (node (ref "C24") (pin "2") (pinfunction "2_2") (pintype "passive"))
      (node (ref "C25") (pin "2") (pinfunction "2_2") (pintype "passive"))
      (node (ref "C26") (pin "2") (pinfunction "2_2") (pintype "passive"))
      (node (ref "C27") (pin "2") (pinfunction "2_2") (pintype "passive"))
      (node (ref "C28") (pin "2") (pinfunction "2_2") (pintype "passive"))
      (node (ref "C29") (pin "2") (pinfunction "2_2") (pintype "passive"))
      (node (ref "C30") (pin "1") (pinfunction "1_1") (pintype "passive"))
      (node (ref "C31") (pin "2") (pinfunction "2_2") (pintype "passive"))
      (node (ref "C32") (pin "2") (pinfunction "2_2") (pintype "passive"))
      (node (ref "C33") (pin "2") (pinfunction "2_2") (pintype "passive"))
      (node (ref "C34") (pin "2") (pinfunction "2_2") (pintype "passive"))
      (node (ref "C35") (pin "2") (pinfunction "2_2") (pintype "passive"))
      (node (ref "C36") (pin "2") (pinfunction "2_2") (pintype "passive"))
      (node (ref "U2") (pin "117") (pinfunction "DVDD_117") (pintype "power_in"))
      (node (ref "U2") (pin "118") (pinfunction "DVDD_118") (pintype "power_in"))
      (node (ref "U2") (pin "12") (pinfunction "DVDD_12") (pintype "power_in"))
      (node (ref "U2") (pin "17") (pinfunction "DVDD_17") (pintype "power_in"))
      (node (ref "U2") (pin "2") (pinfunction "DVDD_2") (pintype "power_in"))
      (node (ref "U2") (pin "23") (pinfunction "DVDD_23") (pintype "power_in"))
      (node (ref "U2") (pin "27") (pinfunction "DVDD_27") (pintype "power_in"))
      (node (ref "U2") (pin "6") (pinfunction "DVDD_6") (pintype "power_in"))
      (node (ref "U2") (pin "78") (pinfunction "DVDD_78") (pintype "power_in"))
      (node (ref "U2") (pin "85") (pinfunction "DVDD_85") (pintype "power_in"))
      (node (ref "U2") (pin "90") (pinfunction "DVDD_90") (pintype "power_in"))
      (node (ref "U2") (pin "96") (pinfunction "DVDD_96") (pintype "power_in"))
    )
    (net (code "84") (name "VCC2V5") (class "Default")
      (node (ref "C14") (pin "2") (pinfunction "2_2") (pintype "passive"))
      (node (ref "C15") (pin "2") (pinfunction "2_2") (pintype "passive"))
      (node (ref "C16") (pin "2") (pinfunction "2_2") (pintype "passive"))
      (node (ref "C17") (pin "2") (pinfunction "2_2") (pintype "passive"))
      (node (ref "C18") (pin "2") (pinfunction "2_2") (pintype "passive"))
      (node (ref "C19") (pin "2") (pinfunction "2_2") (pintype "passive"))
      (node (ref "C20") (pin "1") (pinfunction "1_1") (pintype "passive"))
      (node (ref "C21") (pin "2") (pinfunction "2_2") (pintype "passive"))
      (node (ref "C22") (pin "2") (pinfunction "2_2") (pintype "passive"))
      (node (ref "C23") (pin "2") (pinfunction "2_2") (pintype "passive"))
      (node (ref "L1") (pin "1") (pinfunction "1_1") (pintype "passive"))
      (node (ref "R112") (pin "1") (pinfunction "1_1") (pintype "passive"))
      (node (ref "R113") (pin "1") (pinfunction "1_1") (pintype "passive"))
      (node (ref "R115") (pin "1") (pinfunction "1_1") (pintype "passive"))
      (node (ref "R118") (pin "1") (pinfunction "1_1") (pintype "passive"))
      (node (ref "R15") (pin "1") (pinfunction "1_1") (pintype "passive"))
      (node (ref "R16") (pin "1") (pinfunction "1_1") (pintype "passive"))
      (node (ref "R17") (pin "1") (pinfunction "1_1") (pintype "passive"))
      (node (ref "R2") (pin "1") (pinfunction "1_1") (pintype "passive"))
      (node (ref "R22") (pin "1") (pinfunction "1_1") (pintype "passive"))
      (node (ref "R23") (pin "1") (pinfunction "1_1") (pintype "passive"))
      (node (ref "R24") (pin "2") (pinfunction "2_2") (pintype "passive"))
      (node (ref "R25") (pin "2") (pinfunction "2_2") (pintype "passive"))
      (node (ref "R27") (pin "1") (pinfunction "1_1") (pintype "passive"))
      (node (ref "R28") (pin "1") (pinfunction "1_1") (pintype "passive"))
      (node (ref "R4") (pin "1") (pinfunction "1_1") (pintype "passive"))
      (node (ref "U2") (pin "11") (pinfunction "VDDO_11") (pintype "power_in"))
      (node (ref "U2") (pin "122") (pinfunction "VDDO_122") (pintype "power_in"))
      (node (ref "U2") (pin "30") (pinfunction "VDDO_30") (pintype "power_in"))
      (node (ref "U2") (pin "34") (pinfunction "VDDOX_34") (pintype "power_in"))
      (node (ref "U2") (pin "5") (pinfunction "VDDO_5") (pintype "power_in"))
      (node (ref "U2") (pin "71") (pinfunction "VDDOX_71") (pintype "power_in"))
      (node (ref "U2") (pin "73") (pinfunction "VDDOH_73") (pintype "power_in"))
      (node (ref "U2") (pin "89") (pinfunction "VDDOH_89") (pintype "power_in"))
      (node (ref "U2") (pin "97") (pinfunction "VDDOH_97") (pintype "power_in"))
    )
    (net (code "85") (name "VCC3V3") (class "Default")
      (node (ref "R29") (pin "1") (pinfunction "1_1") (pintype "passive"))
      (node (ref "R30") (pin "1") (pinfunction "1_1") (pintype "passive"))
    )
    (net (code "86") (name "unconnected-(U1A-IO_L3P_0-PadD6)") (class "Default")
      (node (ref "U1") (pin "D6") (pinfunction "IO_L3P_0_D6") (pintype "bidirectional"))
    )
    (net (code "87") (name "unconnected-(U1A-IO_L5P_0-PadC7)") (class "Default")
      (node (ref "U1") (pin "C7") (pinfunction "IO_L5P_0_C7") (pintype "bidirectional"))
    )
    (net (code "88") (name "unconnected-(U1A-IO_L64N_SCP4_0-PadA17)") (class "Default")
      (node (ref "U1") (pin "A17") (pinfunction "IO_L64N_SCP4_0_A17") (pintype "bidirectional"))
    )
    (net (code "89") (name "unconnected-(U1A-IO_L64P_SCP5_0-PadC17)") (class "Default")
      (node (ref "U1") (pin "C17") (pinfunction "IO_L64P_SCP5_0_C17") (pintype "bidirectional"))
    )
    (net (code "90") (name "unconnected-(U1A-IO_L66N_SCP0_0-PadD17)") (class "Default")
      (node (ref "U1") (pin "D17") (pinfunction "IO_L66N_SCP0_0_D17") (pintype "bidirectional"))
    )
    (net (code "91") (name "unconnected-(U1A-IO_L66P_SCP1_0-PadE16)") (class "Default")
      (node (ref "U1") (pin "E16") (pinfunction "IO_L66P_SCP1_0_E16") (pintype "bidirectional"))
    )
    (net (code "92") (name "unconnected-(U2-HADAC--Pad54)") (class "Default")
      (node (ref "U2") (pin "54") (pinfunction "HADAC-_54") (pintype "passive"))
    )
    (net (code "93") (name "unconnected-(U2-HSDAC+-Pad53)") (class "Default")
      (node (ref "U2") (pin "53") (pinfunction "HSDAC+_53") (pintype "passive"))
    )
    (net (code "94") (name "unconnected-(U2-S_CLK+-Pad110)") (class "Default")
      (node (ref "U2") (pin "110") (pinfunction "S_CLK+_110") (pintype "bidirectional"))
    )
    (net (code "95") (name "unconnected-(U2-S_CLK--Pad109)") (class "Default")
      (node (ref "U2") (pin "109") (pinfunction "S_CLK-_109") (pintype "bidirectional"))
    )
    (net (code "96") (name "unconnected-(U2-S_IN+-Pad113)") (class "Default")
      (node (ref "U2") (pin "113") (pinfunction "S_IN+_113") (pintype "input"))
    )
    (net (code "97") (name "unconnected-(U2-S_IN--Pad112)") (class "Default")
      (node (ref "U2") (pin "112") (pinfunction "S_IN-_112") (pintype "input"))
    )
    (net (code "98") (name "unconnected-(U2-S_OUT+-Pad107)") (class "Default")
      (node (ref "U2") (pin "107") (pinfunction "S_OUT+_107") (pintype "output"))
    )
    (net (code "99") (name "unconnected-(U2-S_OUT--Pad105)") (class "Default")
      (node (ref "U2") (pin "105") (pinfunction "S_OUT-_105") (pintype "output"))
    )
    (net (code "100") (name "unconnected-(U2-TCK-Pad70)") (class "Default")
      (node (ref "U2") (pin "70") (pinfunction "TCK_70") (pintype "input"))
    )
    (net (code "101") (name "unconnected-(U2-TDI-Pad67)") (class "Default")
      (node (ref "U2") (pin "67") (pinfunction "TDI_67") (pintype "input"))
    )
    (net (code "102") (name "unconnected-(U2-TDO-Pad72)") (class "Default")
      (node (ref "U2") (pin "72") (pinfunction "TDO_72") (pintype "output"))
    )
    (net (code "103") (name "unconnected-(U2-TMS-Pad69)") (class "Default")
      (node (ref "U2") (pin "69") (pinfunction "TMS_69") (pintype "input"))
    )
  )
)
